# C-Track_V1_R1.net
KiCad netlist of a schematic drawn in EAGLE
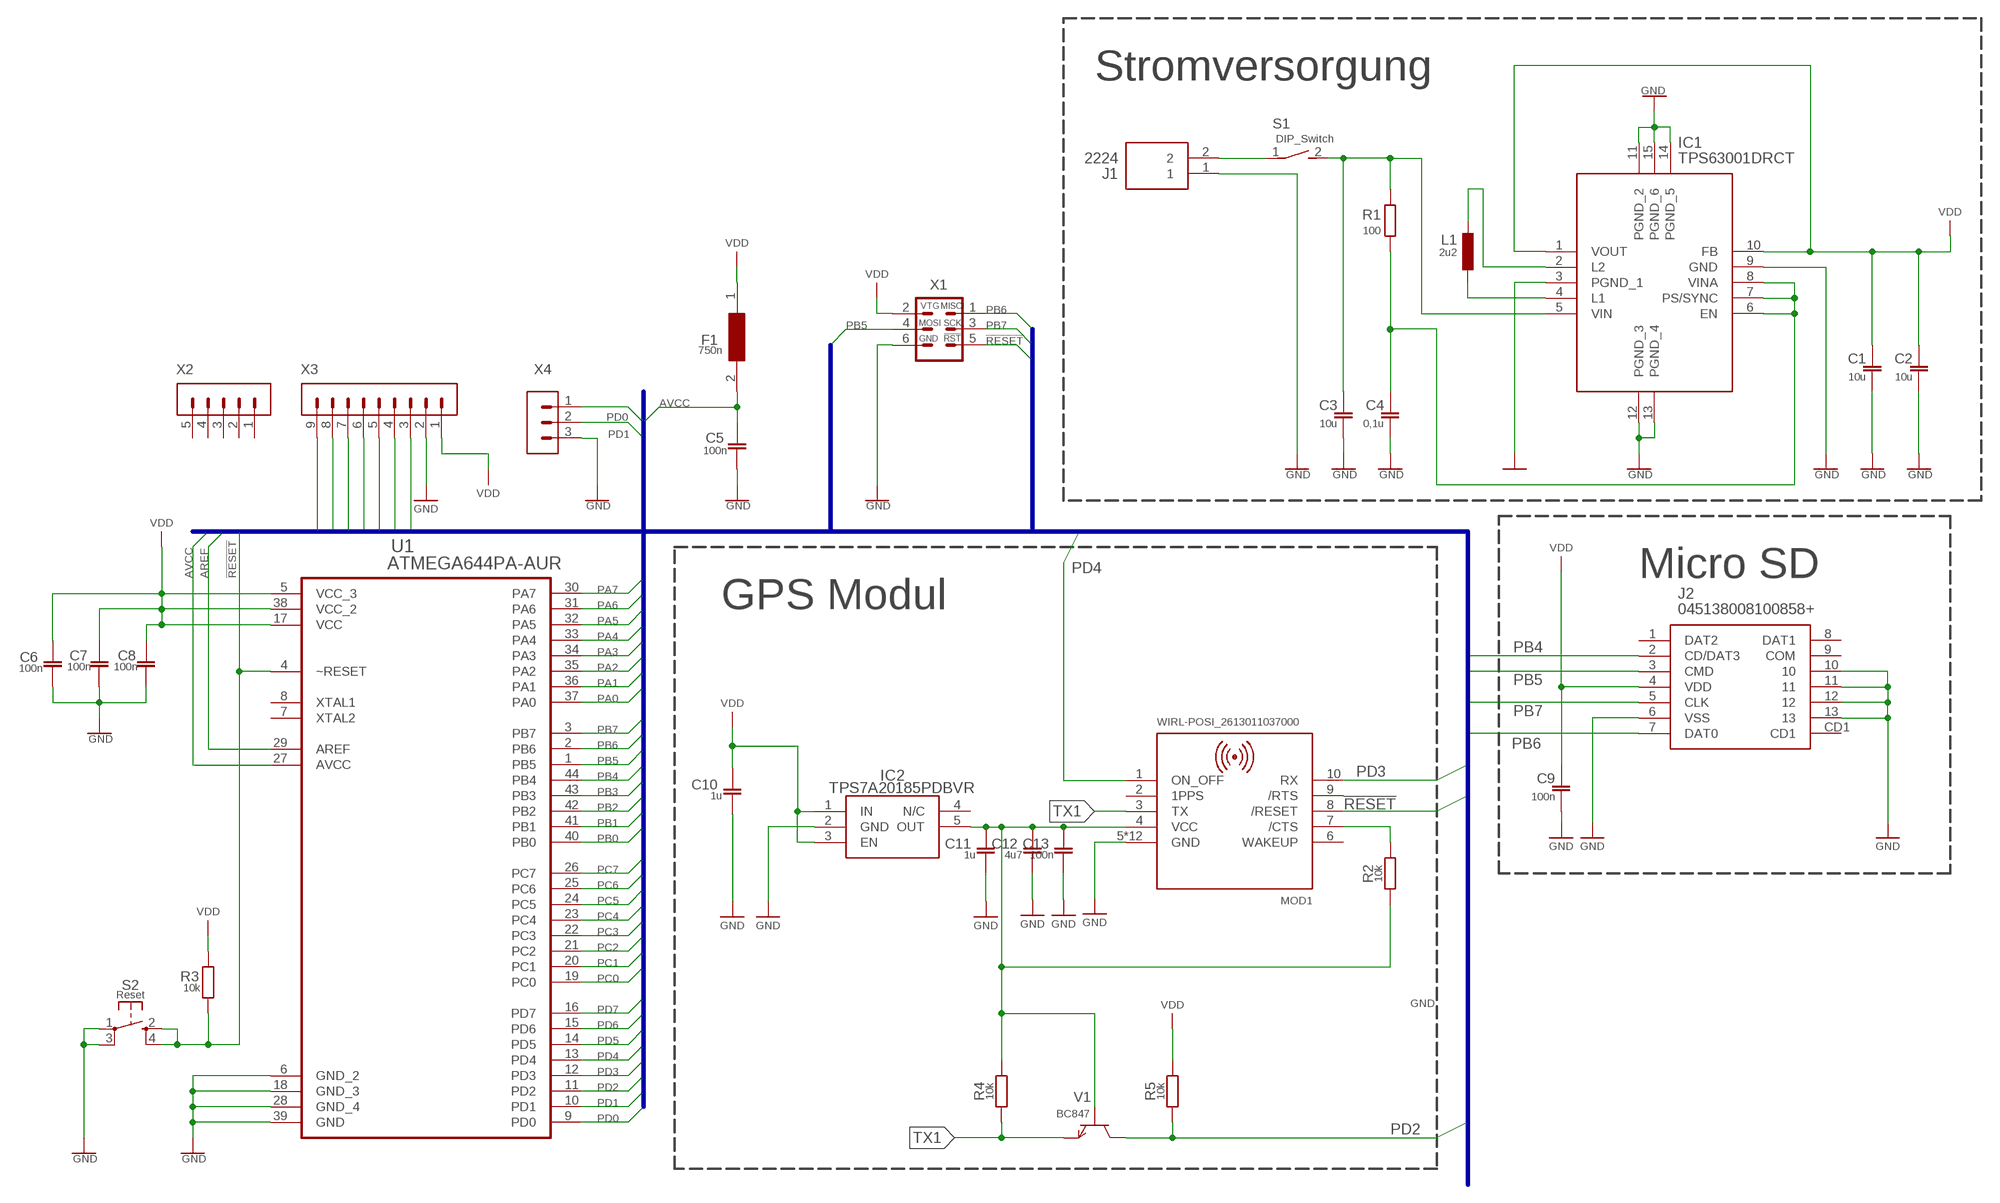
[diagram p0: schematic, sheet 1]

(export (version "E")
  (design (tool "Eeschema 10.0.6"))
  (components
    (comp (ref "C1")
      (value "10u")
      (footprint "eagle-import:C0805")
      (libsource (lib "eagle-import") (part "C-EUC0805"))
    )
    (comp (ref "C2")
      (value "10u")
      (footprint "eagle-import:C0805")
      (libsource (lib "eagle-import") (part "C-EUC0805"))
    )
    (comp (ref "C3")
      (value "10u")
      (footprint "eagle-import:C0805")
      (libsource (lib "eagle-import") (part "C-EUC0805"))
    )
    (comp (ref "C4")
      (value "0,1u")
      (footprint "eagle-import:C0805")
      (libsource (lib "eagle-import") (part "C-EUC0805"))
    )
    (comp (ref "C5")
      (value "100n")
      (footprint "eagle-import:C0805")
      (libsource (lib "eagle-import") (part "C-EUC0805"))
    )
    (comp (ref "C6")
      (value "100n")
      (footprint "eagle-import:C0805")
      (libsource (lib "eagle-import") (part "C-EUC0805"))
    )
    (comp (ref "C7")
      (value "100n")
      (footprint "eagle-import:C0805")
      (libsource (lib "eagle-import") (part "C-EUC0805"))
    )
    (comp (ref "C8")
      (value "100n")
      (footprint "eagle-import:C0805")
      (libsource (lib "eagle-import") (part "C-EUC0805"))
    )
    (comp (ref "C9")
      (value "100n")
      (footprint "eagle-import:C0805")
      (libsource (lib "eagle-import") (part "C-EUC0805"))
    )
    (comp (ref "C10")
      (value "1u")
      (footprint "eagle-import:C0805")
      (libsource (lib "eagle-import") (part "C-EUC0805"))
    )
    (comp (ref "C11")
      (value "1u")
      (footprint "eagle-import:C0805")
      (libsource (lib "eagle-import") (part "C-EUC0805"))
    )
    (comp (ref "C12")
      (value "4u7")
      (footprint "eagle-import:C0805")
      (libsource (lib "eagle-import") (part "C-EUC0805"))
    )
    (comp (ref "C13")
      (value "100n")
      (footprint "eagle-import:C0805")
      (libsource (lib "eagle-import") (part "C-EUC0805"))
    )
    (comp (ref "F1")
      (value "750n")
      (footprint "eagle-import:SF1206HH1200R2")
      (fields
        (field (name "MANUFACTURER_PART_NUMBER") "SF-1206HH1200R-2")
        (field (name "MOUSER_PART_NUMBER") "652-SF-1206HH1200R-2")
      )
      (libsource (lib "eagle-import") (part "SF-1206HH1200R-2"))
    )
    (comp (ref "IC1")
      (value "TPS63001DRCT")
      (footprint "eagle-import:TPS63001DRCT")
      (fields (field (name "MOUSER_PART_NUMBER") "595-TPS63001DRCT"))
      (libsource (lib "eagle-import") (part "TPS63001DRCT"))
    )
    (comp (ref "IC2")
      (value "TPS7A20185PDBVR")
      (footprint "eagle-import:SOT95P280X145-5N")
      (fields (field (name "MOUSER_PART_NUMBER") "595-TPS7A20185PDBVR"))
      (libsource (lib "eagle-import") (part "TPS7A20185PDBVR"))
    )
    (comp (ref "J1")
      (value "2224")
      (footprint "eagle-import:2224")
      (fields (field (name "MOUSER_PART_NUMBER") "534-2224"))
      (libsource (lib "eagle-import") (part "2224"))
    )
    (comp (ref "J2")
      (value "045138008100858+")
      (footprint "eagle-import:045138008100858")
      (fields (field (name "MOUSER_PART_NUMBER") "581-045138008100858+"))
      (libsource (lib "eagle-import") (part "045138008100858+"))
    )
    (comp (ref "L1")
      (value "2u2")
      (footprint "eagle-import:L0805")
      (libsource (lib "eagle-import") (part "L-EU0805"))
    )
    (comp (ref "MOD1")
      (value "WIRL-POSI_2613011037000")
      (footprint "eagle-import:WIRL-POSI_2613011037000")
      (fields (field (name "MANUFACTURER") "Würth Elektronik"))
      (libsource (lib "eagle-import") (part "WIRL-POSI_2613011037000"))
    )
    (comp (ref "R1")
      (value "100")
      (footprint "eagle-import:M0805")
      (libsource (lib "eagle-import") (part "R-EU_M0805"))
    )
    (comp (ref "R2")
      (value "10k")
      (footprint "eagle-import:M0805")
      (libsource (lib "eagle-import") (part "R-EU_M0805"))
    )
    (comp (ref "R3")
      (value "10k")
      (footprint "eagle-import:M0805")
      (libsource (lib "eagle-import") (part "R-EU_M0805"))
    )
    (comp (ref "R4")
      (value "10k")
      (footprint "eagle-import:M0805")
      (libsource (lib "eagle-import") (part "R-EU_M0805"))
    )
    (comp (ref "R5")
      (value "10k")
      (footprint "eagle-import:M0805")
      (libsource (lib "eagle-import") (part "R-EU_M0805"))
    )
    (comp (ref "S1")
      (value "DIP_Switch")
      (footprint "eagle-import:DS04254201BKSMT")
      (fields
        (field (name "MANUFACTURER_PART_NUMBER") "DS04-254-2-01BK-SMT")
        (field (name "MOUSER_PART_NUMBER") "490-DS04254201BK-SMT")
      )
      (libsource (lib "eagle-import") (part "DS04-254-2-01BK-SMT"))
    )
    (comp (ref "S2")
      (value "Reset")
      (footprint "eagle-import:WS-TASV-MICRO")
      (libsource (lib "eagle-import") (part "TASTE10-XXWE_TASV_MICRO"))
    )
    (comp (ref "U1")
      (value "ATMEGA644PA-AUR")
      (footprint "eagle-import:QFP80P1200X1200X120-44N")
      (fields (field (name "MF") "Microchip"))
      (libsource (lib "eagle-import") (part "ATMEGA644PA-AUR"))
    )
    (comp (ref "V1")
      (value "BC847")
      (footprint "eagle-import:SOT23")
      (libsource (lib "eagle-import") (part "BC847"))
    )
    (comp (ref "X1")
      (value "MA03-2-")
      (footprint "eagle-import:MA03-2-")
      (libsource (lib "eagle-import") (part "MA03-2-"))
    )
    (comp (ref "X2")
      (value "MA05-1")
      (footprint "eagle-import:MA05-1")
      (libsource (lib "eagle-import") (part "MA05-1"))
    )
    (comp (ref "X3")
      (value "MA09-1MA-09-1")
      (footprint "eagle-import:MA09-1")
      (libsource (lib "eagle-import") (part "MA09-1MA-09-1"))
    )
    (comp (ref "X4")
      (value "MA03-1")
      (footprint "eagle-import:MA03-1")
      (libsource (lib "eagle-import") (part "MA03-1"))
    )
  )
  (nets
    (net (code "3") (name "AREF") (class "Default")
      (node (ref "U1") (pin "29") (pinfunction "AREF_29") (pintype "input"))
    )
    (net (code "4") (name "AVCC") (class "Default")
      (node (ref "C5") (pin "1") (pinfunction "1_1") (pintype "passive"))
      (node (ref "F1") (pin "2") (pinfunction "2_2") (pintype "bidirectional"))
      (node (ref "U1") (pin "27") (pinfunction "AVCC_27") (pintype "power_in"))
    )
    (net (code "5") (name "GND") (class "Default")
      (node (ref "C1") (pin "2") (pinfunction "2_2") (pintype "passive"))
      (node (ref "C10") (pin "2") (pinfunction "2_2") (pintype "passive"))
      (node (ref "C11") (pin "2") (pinfunction "2_2") (pintype "passive"))
      (node (ref "C12") (pin "2") (pinfunction "2_2") (pintype "passive"))
      (node (ref "C13") (pin "2") (pinfunction "2_2") (pintype "passive"))
      (node (ref "C2") (pin "2") (pinfunction "2_2") (pintype "passive"))
      (node (ref "C3") (pin "2") (pinfunction "2_2") (pintype "passive"))
      (node (ref "C4") (pin "2") (pinfunction "2_2") (pintype "passive"))
      (node (ref "C5") (pin "2") (pinfunction "2_2") (pintype "passive"))
      (node (ref "C6") (pin "2") (pinfunction "2_2") (pintype "passive"))
      (node (ref "C7") (pin "2") (pinfunction "2_2") (pintype "passive"))
      (node (ref "C8") (pin "2") (pinfunction "2_2") (pintype "passive"))
      (node (ref "C9") (pin "2") (pinfunction "2_2") (pintype "passive"))
      (node (ref "IC1") (pin "11") (pinfunction "PGND_2_11") (pintype "bidirectional"))
      (node (ref "IC1") (pin "12") (pinfunction "PGND_3_12") (pintype "bidirectional"))
      (node (ref "IC1") (pin "13") (pinfunction "PGND_4_13") (pintype "bidirectional"))
      (node (ref "IC1") (pin "14") (pinfunction "PGND_5_14") (pintype "bidirectional"))
      (node (ref "IC1") (pin "15") (pinfunction "PGND_6_15") (pintype "bidirectional"))
      (node (ref "IC1") (pin "3") (pinfunction "PGND_1_3") (pintype "bidirectional"))
      (node (ref "IC1") (pin "9") (pinfunction "GND_9") (pintype "bidirectional"))
      (node (ref "IC2") (pin "2") (pinfunction "GND_2") (pintype "bidirectional"))
      (node (ref "J1") (pin "1") (pinfunction "1_1") (pintype "bidirectional"))
      (node (ref "J2") (pin "10") (pinfunction "10_10") (pintype "bidirectional"))
      (node (ref "J2") (pin "11") (pinfunction "11_11") (pintype "bidirectional"))
      (node (ref "J2") (pin "12") (pinfunction "12_12") (pintype "bidirectional"))
      (node (ref "J2") (pin "13") (pinfunction "13_13") (pintype "bidirectional"))
      (node (ref "J2") (pin "6") (pinfunction "VSS_6") (pintype "bidirectional"))
      (node (ref "MOD1") (pin "5") (pinfunction "GND_5") (pintype "bidirectional"))
      (node (ref "MOD1") (pin "P$1") (pinfunction "GND_P$1") (pintype "bidirectional"))
      (node (ref "MOD1") (pin "P$10") (pinfunction "GND_P$10") (pintype "bidirectional"))
      (node (ref "MOD1") (pin "P$11") (pinfunction "GND_P$11") (pintype "bidirectional"))
      (node (ref "MOD1") (pin "P$2") (pinfunction "GND_P$2") (pintype "bidirectional"))
      (node (ref "MOD1") (pin "P$3") (pinfunction "GND_P$3") (pintype "bidirectional"))
      (node (ref "MOD1") (pin "P$4") (pinfunction "GND_P$4") (pintype "bidirectional"))
      (node (ref "MOD1") (pin "P$5") (pinfunction "GND_P$5") (pintype "bidirectional"))
      (node (ref "MOD1") (pin "P$6") (pinfunction "GND_P$6") (pintype "bidirectional"))
      (node (ref "MOD1") (pin "P$7") (pinfunction "GND_P$7") (pintype "bidirectional"))
      (node (ref "MOD1") (pin "P$8") (pinfunction "GND_P$8") (pintype "bidirectional"))
      (node (ref "MOD1") (pin "P$9") (pinfunction "GND_P$9") (pintype "bidirectional"))
      (node (ref "S2") (pin "1") (pinfunction "P_1") (pintype "passive"))
      (node (ref "S2") (pin "3") (pinfunction "P1_3") (pintype "passive"))
      (node (ref "U1") (pin "18") (pinfunction "GND_3_18") (pintype "passive"))
      (node (ref "U1") (pin "28") (pinfunction "GND_4_28") (pintype "passive"))
      (node (ref "U1") (pin "39") (pinfunction "GND_39") (pintype "passive"))
      (node (ref "U1") (pin "6") (pinfunction "GND_2_6") (pintype "passive"))
      (node (ref "X1") (pin "6") (pinfunction "6_6") (pintype "passive"))
      (node (ref "X3") (pin "2") (pinfunction "1_2") (pintype "passive"))
      (node (ref "X4") (pin "3") (pinfunction "3_3") (pintype "passive"))
    )
    (net (code "6") (name "Net-(IC1-EN)") (class "Default")
      (node (ref "C4") (pin "1") (pinfunction "1_1") (pintype "passive"))
      (node (ref "IC1") (pin "6") (pinfunction "EN_6") (pintype "bidirectional"))
      (node (ref "IC1") (pin "7") (pinfunction "PS/SYNC_7") (pintype "bidirectional"))
      (node (ref "IC1") (pin "8") (pinfunction "VINA_8") (pintype "bidirectional"))
      (node (ref "R1") (pin "1") (pinfunction "1_1") (pintype "passive"))
    )
    (net (code "7") (name "Net-(IC1-L1)") (class "Default")
      (node (ref "IC1") (pin "4") (pinfunction "L1_4") (pintype "bidirectional"))
      (node (ref "L1") (pin "1") (pinfunction "1_1") (pintype "passive"))
    )
    (net (code "8") (name "Net-(IC1-L2)") (class "Default")
      (node (ref "IC1") (pin "2") (pinfunction "L2_2") (pintype "bidirectional"))
      (node (ref "L1") (pin "2") (pinfunction "2_2") (pintype "passive"))
    )
    (net (code "9") (name "Net-(IC1-VIN)") (class "Default")
      (node (ref "C3") (pin "1") (pinfunction "1_1") (pintype "passive"))
      (node (ref "IC1") (pin "5") (pinfunction "VIN_5") (pintype "bidirectional"))
      (node (ref "R1") (pin "2") (pinfunction "2_2") (pintype "passive"))
      (node (ref "S1") (pin "2") (pinfunction "2_2") (pintype "passive"))
    )
    (net (code "10") (name "Net-(IC2-OUT)") (class "Default")
      (node (ref "C11") (pin "1") (pinfunction "1_1") (pintype "passive"))
      (node (ref "C12") (pin "1") (pinfunction "1_1") (pintype "passive"))
      (node (ref "C13") (pin "1") (pinfunction "1_1") (pintype "passive"))
      (node (ref "IC2") (pin "5") (pinfunction "OUT_5") (pintype "bidirectional"))
      (node (ref "MOD1") (pin "4") (pinfunction "VCC_4") (pintype "bidirectional"))
      (node (ref "R2") (pin "1") (pinfunction "1_1") (pintype "passive"))
      (node (ref "R4") (pin "2") (pinfunction "2_2") (pintype "passive"))
      (node (ref "V1") (pin "1") (pinfunction "B_1") (pintype "passive"))
    )
    (net (code "11") (name "Net-(J1-Pad2)") (class "Default")
      (node (ref "J1") (pin "2") (pinfunction "2_2") (pintype "bidirectional"))
      (node (ref "S1") (pin "1") (pinfunction "1_1") (pintype "passive"))
    )
    (net (code "12") (name "Net-(MOD1-{slash}CTS)") (class "Default")
      (node (ref "MOD1") (pin "7") (pinfunction "/CTS_7") (pintype "bidirectional"))
      (node (ref "R2") (pin "2") (pinfunction "2_2") (pintype "passive"))
    )
    (net (code "13") (name "PA0") (class "Default")
      (node (ref "U1") (pin "37") (pinfunction "PA0_37") (pintype "bidirectional"))
    )
    (net (code "14") (name "PA1") (class "Default")
      (node (ref "U1") (pin "36") (pinfunction "PA1_36") (pintype "bidirectional"))
    )
    (net (code "15") (name "PA2") (class "Default")
      (node (ref "U1") (pin "35") (pinfunction "PA2_35") (pintype "bidirectional"))
    )
    (net (code "16") (name "PA3") (class "Default")
      (node (ref "U1") (pin "34") (pinfunction "PA3_34") (pintype "bidirectional"))
    )
    (net (code "17") (name "PA4") (class "Default")
      (node (ref "U1") (pin "33") (pinfunction "PA4_33") (pintype "bidirectional"))
    )
    (net (code "18") (name "PA5") (class "Default")
      (node (ref "U1") (pin "32") (pinfunction "PA5_32") (pintype "bidirectional"))
    )
    (net (code "19") (name "PA6") (class "Default")
      (node (ref "U1") (pin "31") (pinfunction "PA6_31") (pintype "bidirectional"))
      (node (ref "X3") (pin "8") (pinfunction "7_8") (pintype "passive"))
    )
    (net (code "20") (name "PA7") (class "Default")
      (node (ref "U1") (pin "30") (pinfunction "PA7_30") (pintype "bidirectional"))
      (node (ref "X3") (pin "3") (pinfunction "2_3") (pintype "passive"))
    )
    (net (code "21") (name "PB0") (class "Default")
      (node (ref "U1") (pin "40") (pinfunction "PB0_40") (pintype "bidirectional"))
    )
    (net (code "22") (name "PB1") (class "Default")
      (node (ref "U1") (pin "41") (pinfunction "PB1_41") (pintype "bidirectional"))
    )
    (net (code "23") (name "PB2") (class "Default")
      (node (ref "U1") (pin "42") (pinfunction "PB2_42") (pintype "bidirectional"))
      (node (ref "X3") (pin "4") (pinfunction "3_4") (pintype "passive"))
    )
    (net (code "24") (name "PB3") (class "Default")
      (node (ref "U1") (pin "43") (pinfunction "PB3_43") (pintype "bidirectional"))
    )
    (net (code "25") (name "PB4") (class "Default")
      (node (ref "J2") (pin "2") (pinfunction "CD/DAT3_2") (pintype "bidirectional"))
      (node (ref "U1") (pin "44") (pinfunction "PB4_44") (pintype "bidirectional"))
    )
    (net (code "26") (name "PB5") (class "Default")
      (node (ref "J2") (pin "3") (pinfunction "CMD_3") (pintype "bidirectional"))
      (node (ref "U1") (pin "1") (pinfunction "PB5_1") (pintype "bidirectional"))
      (node (ref "X1") (pin "4") (pinfunction "4_4") (pintype "passive"))
      (node (ref "X3") (pin "7") (pinfunction "6_7") (pintype "passive"))
    )
    (net (code "27") (name "PB6") (class "Default")
      (node (ref "J2") (pin "7") (pinfunction "DAT0_7") (pintype "bidirectional"))
      (node (ref "U1") (pin "2") (pinfunction "PB6_2") (pintype "bidirectional"))
      (node (ref "X1") (pin "1") (pinfunction "1_1") (pintype "passive"))
      (node (ref "X3") (pin "6") (pinfunction "5_6") (pintype "passive"))
    )
    (net (code "28") (name "PB7") (class "Default")
      (node (ref "J2") (pin "5") (pinfunction "CLK_5") (pintype "bidirectional"))
      (node (ref "U1") (pin "3") (pinfunction "PB7_3") (pintype "bidirectional"))
      (node (ref "X1") (pin "3") (pinfunction "3_3") (pintype "passive"))
      (node (ref "X3") (pin "5") (pinfunction "4_5") (pintype "passive"))
    )
    (net (code "29") (name "PC0") (class "Default")
      (node (ref "U1") (pin "19") (pinfunction "PC0_19") (pintype "bidirectional"))
    )
    (net (code "30") (name "PC1") (class "Default")
      (node (ref "U1") (pin "20") (pinfunction "PC1_20") (pintype "bidirectional"))
    )
    (net (code "31") (name "PC2") (class "Default")
      (node (ref "U1") (pin "21") (pinfunction "PC2_21") (pintype "bidirectional"))
    )
    (net (code "32") (name "PC3") (class "Default")
      (node (ref "U1") (pin "22") (pinfunction "PC3_22") (pintype "bidirectional"))
    )
    (net (code "33") (name "PC4") (class "Default")
      (node (ref "U1") (pin "23") (pinfunction "PC4_23") (pintype "bidirectional"))
    )
    (net (code "34") (name "PC5") (class "Default")
      (node (ref "U1") (pin "24") (pinfunction "PC5_24") (pintype "bidirectional"))
    )
    (net (code "35") (name "PC6") (class "Default")
      (node (ref "U1") (pin "25") (pinfunction "PC6_25") (pintype "bidirectional"))
    )
    (net (code "36") (name "PC7") (class "Default")
      (node (ref "U1") (pin "26") (pinfunction "PC7_26") (pintype "bidirectional"))
    )
    (net (code "37") (name "PD0") (class "Default")
      (node (ref "U1") (pin "9") (pinfunction "PD0_9") (pintype "bidirectional"))
      (node (ref "X4") (pin "1") (pinfunction "1_1") (pintype "passive"))
    )
    (net (code "38") (name "PD1") (class "Default")
      (node (ref "U1") (pin "10") (pinfunction "PD1_10") (pintype "bidirectional"))
      (node (ref "X4") (pin "2") (pinfunction "2_2") (pintype "passive"))
    )
    (net (code "39") (name "PD2") (class "Default")
      (node (ref "R5") (pin "1") (pinfunction "1_1") (pintype "passive"))
      (node (ref "U1") (pin "11") (pinfunction "PD2_11") (pintype "bidirectional"))
      (node (ref "V1") (pin "3") (pinfunction "C_3") (pintype "passive"))
    )
    (net (code "40") (name "PD3") (class "Default")
      (node (ref "MOD1") (pin "10") (pinfunction "RX_10") (pintype "bidirectional"))
      (node (ref "U1") (pin "12") (pinfunction "PD3_12") (pintype "bidirectional"))
    )
    (net (code "41") (name "PD4") (class "Default")
      (node (ref "MOD1") (pin "1") (pinfunction "ON_OFF_1") (pintype "bidirectional"))
      (node (ref "U1") (pin "13") (pinfunction "PD4_13") (pintype "bidirectional"))
    )
    (net (code "42") (name "PD5") (class "Default")
      (node (ref "U1") (pin "14") (pinfunction "PD5_14") (pintype "bidirectional"))
    )
    (net (code "43") (name "PD6") (class "Default")
      (node (ref "U1") (pin "15") (pinfunction "PD6_15") (pintype "bidirectional"))
    )
    (net (code "44") (name "PD7") (class "Default")
      (node (ref "U1") (pin "16") (pinfunction "PD7_16") (pintype "bidirectional"))
    )
    (net (code "45") (name "TX1") (class "Default")
      (node (ref "MOD1") (pin "3") (pinfunction "TX_3") (pintype "bidirectional"))
      (node (ref "R4") (pin "1") (pinfunction "1_1") (pintype "passive"))
      (node (ref "V1") (pin "2") (pinfunction "E_2") (pintype "passive"))
    )
    (net (code "46") (name "VDD") (class "Default")
      (node (ref "C1") (pin "1") (pinfunction "1_1") (pintype "passive"))
      (node (ref "C10") (pin "1") (pinfunction "1_1") (pintype "passive"))
      (node (ref "C2") (pin "1") (pinfunction "1_1") (pintype "passive"))
      (node (ref "C6") (pin "1") (pinfunction "1_1") (pintype "passive"))
      (node (ref "C7") (pin "1") (pinfunction "1_1") (pintype "passive"))
      (node (ref "C8") (pin "1") (pinfunction "1_1") (pintype "passive"))
      (node (ref "C9") (pin "1") (pinfunction "1_1") (pintype "passive"))
      (node (ref "F1") (pin "1") (pinfunction "1_1") (pintype "bidirectional"))
      (node (ref "IC1") (pin "1") (pinfunction "VOUT_1") (pintype "bidirectional"))
      (node (ref "IC1") (pin "10") (pinfunction "FB_10") (pintype "bidirectional"))
      (node (ref "IC2") (pin "1") (pinfunction "IN_1") (pintype "bidirectional"))
      (node (ref "IC2") (pin "3") (pinfunction "EN_3") (pintype "bidirectional"))
      (node (ref "J2") (pin "4") (pinfunction "VDD_4") (pintype "bidirectional"))
      (node (ref "R3") (pin "2") (pinfunction "2_2") (pintype "passive"))
      (node (ref "R5") (pin "2") (pinfunction "2_2") (pintype "passive"))
      (node (ref "U1") (pin "17") (pinfunction "VCC_17") (pintype "power_in"))
      (node (ref "U1") (pin "38") (pinfunction "VCC_2_38") (pintype "power_in"))
      (node (ref "U1") (pin "5") (pinfunction "VCC_3_5") (pintype "power_in"))
      (node (ref "X1") (pin "2") (pinfunction "2_2") (pintype "passive"))
      (node (ref "X3") (pin "1") (pinfunction "0_1") (pintype "passive"))
    )
    (net (code "47") (name "unconnected-(IC2-N{slash}C-Pad4)") (class "Default")
      (node (ref "IC2") (pin "4") (pinfunction "N/C_4") (pintype "no_connect"))
    )
    (net (code "48") (name "unconnected-(J2-COM-Pad9)") (class "Default")
      (node (ref "J2") (pin "9") (pinfunction "COM_9") (pintype "bidirectional"))
    )
    (net (code "49") (name "unconnected-(J2-DAT1-Pad8)") (class "Default")
      (node (ref "J2") (pin "8") (pinfunction "DAT1_8") (pintype "bidirectional"))
    )
    (net (code "50") (name "unconnected-(J2-DAT2-Pad1)") (class "Default")
      (node (ref "J2") (pin "1") (pinfunction "DAT2_1") (pintype "bidirectional"))
    )
    (net (code "51") (name "unconnected-(J2-PadCD1)") (class "Default")
      (node (ref "J2") (pin "CD1") (pinfunction "CD1_CD1") (pintype "bidirectional"))
    )
    (net (code "52") (name "unconnected-(MOD1-1PPS-Pad2)") (class "Default")
      (node (ref "MOD1") (pin "2") (pinfunction "1PPS_2") (pintype "bidirectional"))
    )
    (net (code "53") (name "unconnected-(MOD1-WAKEUP-Pad6)") (class "Default")
      (node (ref "MOD1") (pin "6") (pinfunction "WAKEUP_6") (pintype "bidirectional"))
    )
    (net (code "54") (name "unconnected-(MOD1-{slash}RTS-Pad9)") (class "Default")
      (node (ref "MOD1") (pin "9") (pinfunction "/RTS_9") (pintype "bidirectional"))
    )
    (net (code "55") (name "unconnected-(U1-XTAL1-Pad8)") (class "Default")
      (node (ref "U1") (pin "8") (pinfunction "XTAL1_8") (pintype "input"))
    )
    (net (code "56") (name "unconnected-(U1-XTAL2-Pad7)") (class "Default")
      (node (ref "U1") (pin "7") (pinfunction "XTAL2_7") (pintype "output"))
    )
    (net (code "57") (name "unconnected-(X2-0-Pad1)") (class "Default")
      (node (ref "X2") (pin "1") (pinfunction "0_1") (pintype "passive"))
    )
    (net (code "58") (name "unconnected-(X2-1-Pad2)") (class "Default")
      (node (ref "X2") (pin "2") (pinfunction "1_2") (pintype "passive"))
    )
    (net (code "59") (name "unconnected-(X2-2-Pad3)") (class "Default")
      (node (ref "X2") (pin "3") (pinfunction "2_3") (pintype "passive"))
    )
    (net (code "60") (name "unconnected-(X2-3-Pad4)") (class "Default")
      (node (ref "X2") (pin "4") (pinfunction "3_4") (pintype "passive"))
    )
    (net (code "61") (name "unconnected-(X2-4-Pad5)") (class "Default")
      (node (ref "X2") (pin "5") (pinfunction "4_5") (pintype "passive"))
    )
    (net (code "62") (name "~{RESET}") (class "Default")
      (node (ref "MOD1") (pin "8") (pinfunction "/RESET_8") (pintype "bidirectional"))
      (node (ref "R3") (pin "1") (pinfunction "1_1") (pintype "passive"))
      (node (ref "S2") (pin "2") (pinfunction "S_2") (pintype "passive"))
      (node (ref "S2") (pin "4") (pinfunction "S1_4") (pintype "passive"))
      (node (ref "U1") (pin "4") (pinfunction "~{RESET}_4") (pintype "input"))
      (node (ref "X1") (pin "5") (pinfunction "5_5") (pintype "passive"))
      (node (ref "X3") (pin "9") (pinfunction "8_9") (pintype "passive"))
    )
  )
)
